# 4_PowerSupplie.net
KiCad netlist of a schematic drawn in Altium Designer
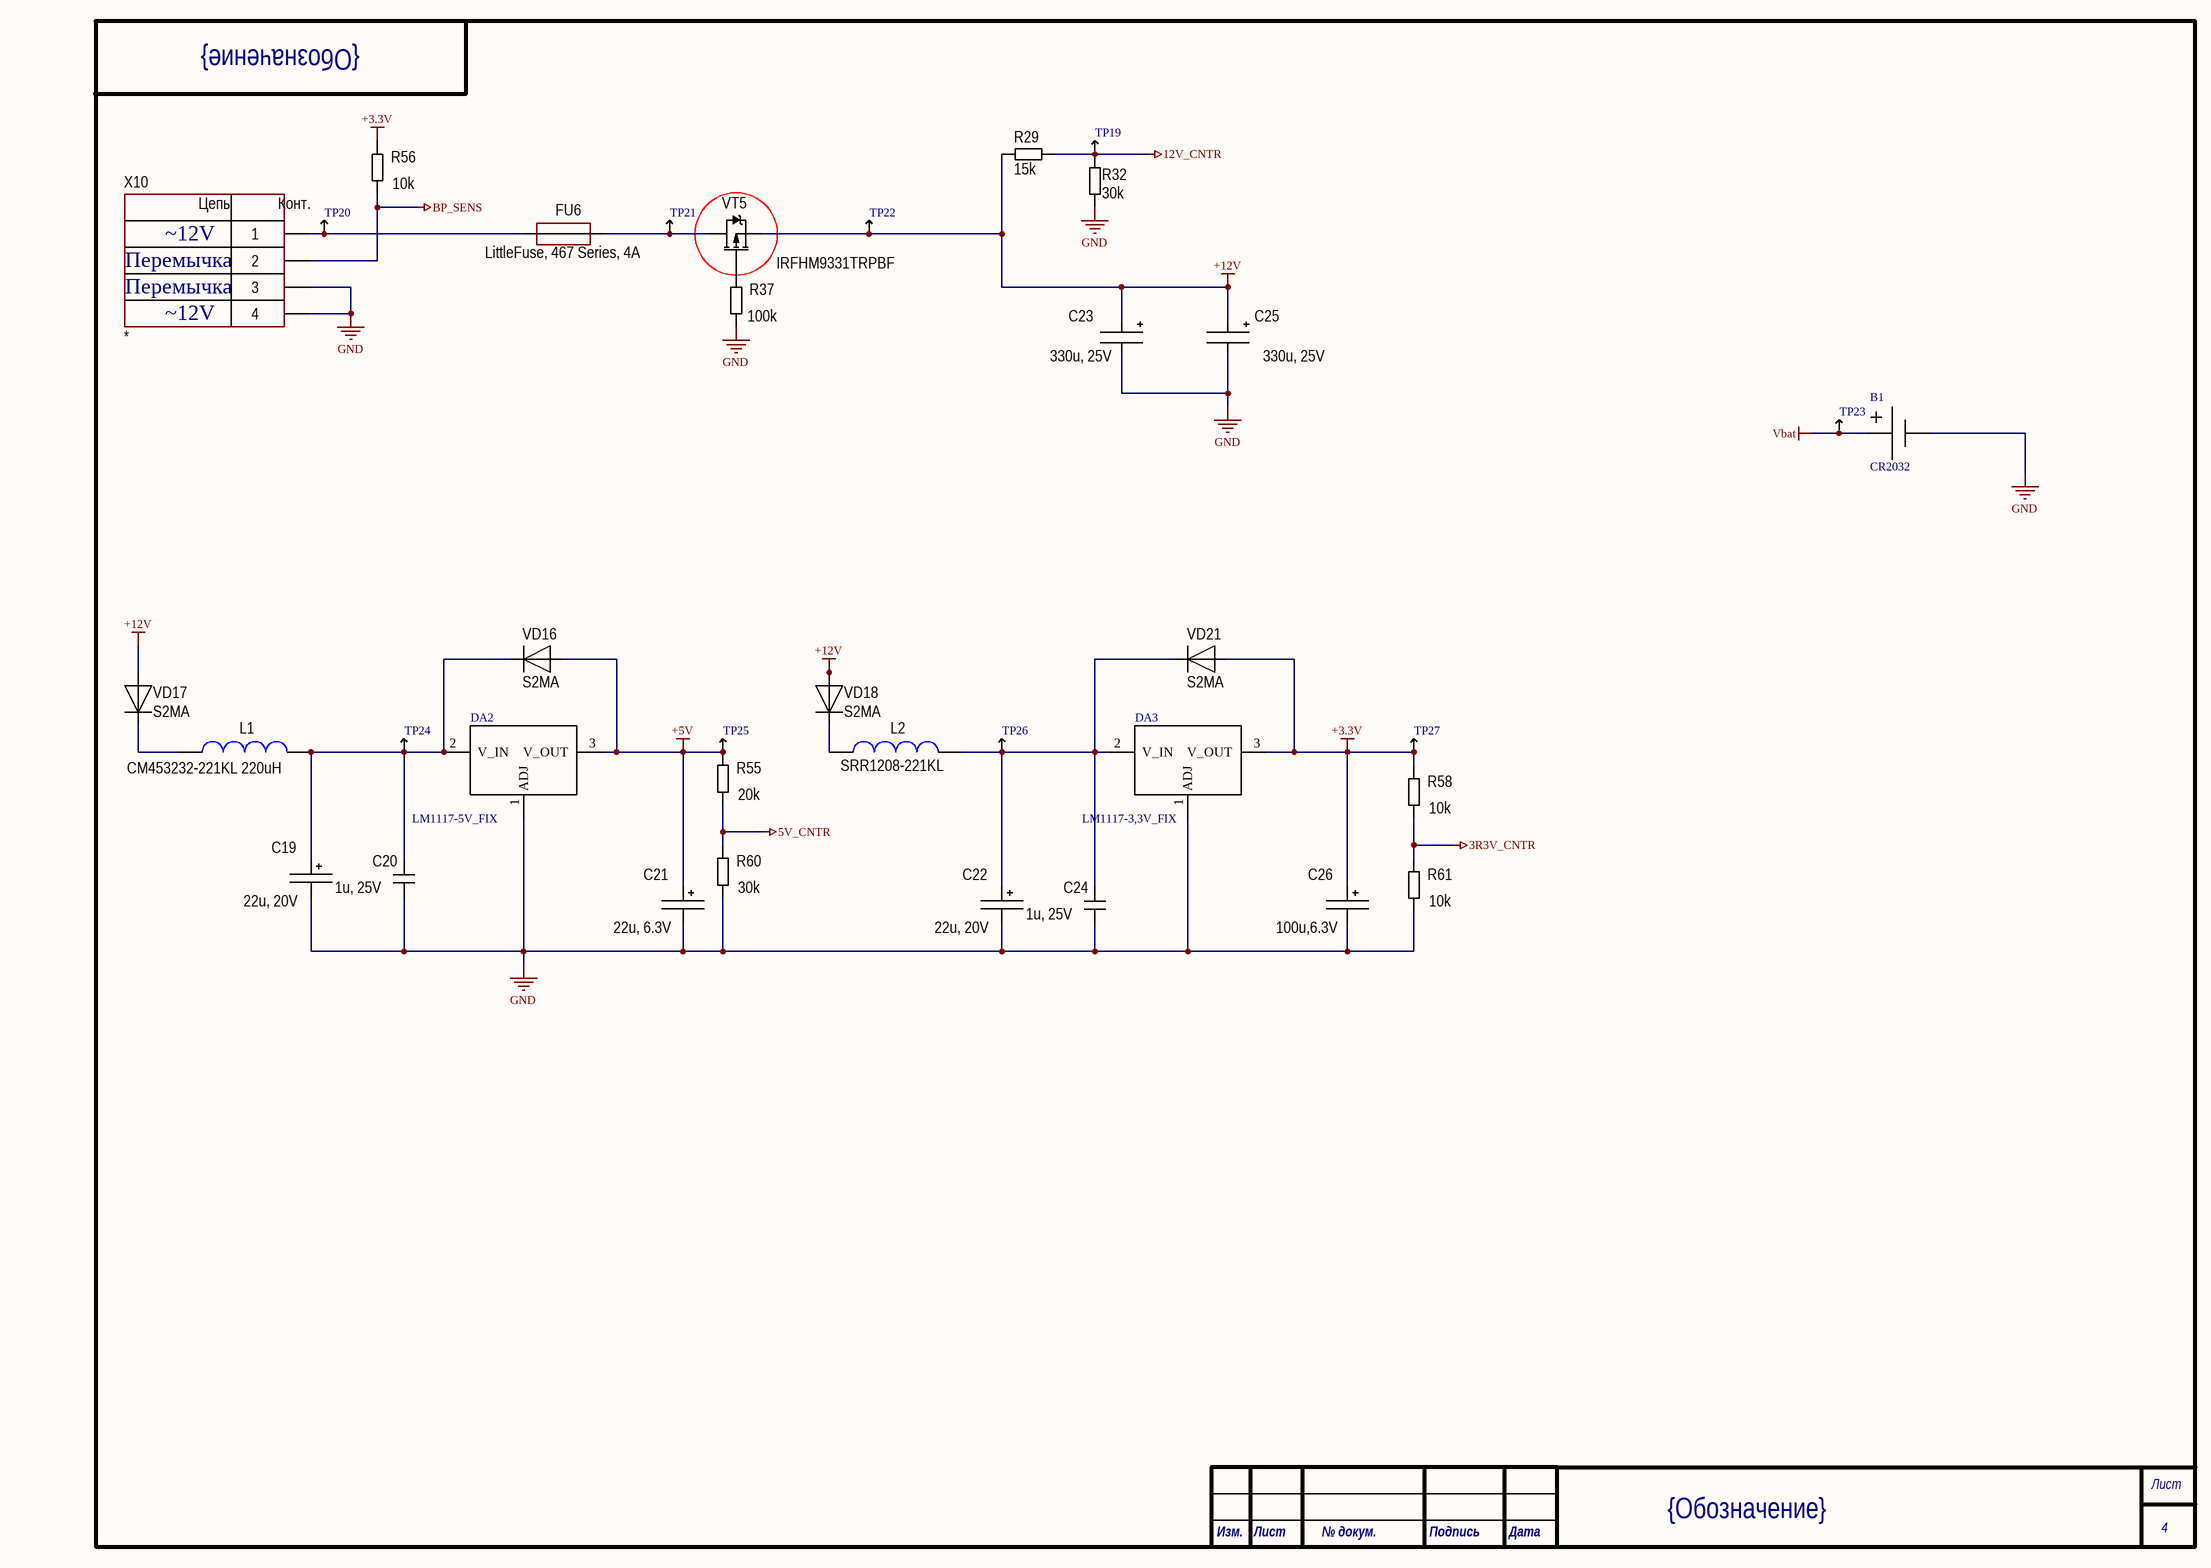
[diagram p0: 4_PowerSupplie.SchDoc]

(export (version "E")
  (design (tool "Eeschema 10.0.6"))
  (components
    (comp (ref "B1")
      (value "CR2032")
      (footprint "CR2032")
      (libsource (lib "Melochi") (part "Battery_CR2032"))
    )
    (comp (ref "C19")
      (value "22u, 20V")
      (footprint "TANTAL_B")
      (libsource (lib "Condensators") (part "TantalCap"))
    )
    (comp (ref "C20")
      (value "1u, 25V")
      (footprint "CH0805C")
      (libsource (lib "Condensators") (part "Capacitor"))
    )
    (comp (ref "C21")
      (value "22u, 6.3V")
      (footprint "TANTAL_B")
      (libsource (lib "Condensators") (part "TantalCap"))
    )
    (comp (ref "C22")
      (value "22u, 20V")
      (footprint "TANTAL_B")
      (libsource (lib "Condensators") (part "TantalCap"))
    )
    (comp (ref "C23")
      (value "330u, 25V")
      (footprint "D10C4.4H10")
      (libsource (lib "Condensators") (part "AlumCap"))
    )
    (comp (ref "C24")
      (value "1u, 25V")
      (footprint "CH0805C")
      (libsource (lib "Condensators") (part "Capacitor"))
    )
    (comp (ref "C25")
      (value "330u, 25V")
      (footprint "D10C4.4H10")
      (libsource (lib "Condensators") (part "AlumCap"))
    )
    (comp (ref "C26")
      (value "100u,6.3V")
      (footprint "TANTAL_B")
      (libsource (lib "Condensators") (part "TantalCap"))
    )
    (comp (ref "DA2")
      (value "LM1117-5V_FIX")
      (footprint "SOT223_123")
      (libsource (lib "MicroIC") (part "LM1117"))
    )
    (comp (ref "DA3")
      (value "LM1117-3,3V_FIX")
      (footprint "SOT223_123")
      (libsource (lib "MicroIC") (part "LM1117"))
    )
    (comp (ref "FU6")
      (value "LittleFuse, 467 Series, 4A")
      (footprint "CH0603F")
      (libsource (lib "Melochi") (part "Fuse"))
    )
    (comp (ref "L1")
      (value "CM453232-221KL 220uH")
      (footprint "IND:1812")
      (libsource (lib "Inductance") (part "Inductor"))
    )
    (comp (ref "L2")
      (value "SRR1208-221KL")
      (footprint "IND: SRR1208")
      (libsource (lib "Inductance") (part "Inductor"))
    )
    (comp (ref "R29") (value "15k") (footprint "CH0805R") (libsource (lib "Resistors") (part "Resistor")))
    (comp (ref "R32") (value "30k") (footprint "CH0805R") (libsource (lib "Resistors") (part "Resistor")))
    (comp (ref "R37") (value "100k") (footprint "CH0805R") (libsource (lib "Resistors") (part "Resistor")))
    (comp (ref "R55") (value "20k") (footprint "CH0805R") (libsource (lib "Resistors") (part "Resistor")))
    (comp (ref "R56") (value "10k") (footprint "CH0805R") (libsource (lib "Resistors") (part "Resistor")))
    (comp (ref "R58") (value "10k") (footprint "CH0805R") (libsource (lib "Resistors") (part "Resistor")))
    (comp (ref "R60") (value "30k") (footprint "CH0805R") (libsource (lib "Resistors") (part "Resistor")))
    (comp (ref "R61") (value "10k") (footprint "CH0805R") (libsource (lib "Resistors") (part "Resistor")))
    (comp (ref "TP19") (value "TestPoint") (libsource (lib "BufLib") (part "TestPoint")))
    (comp (ref "TP20") (value "TestPoint") (libsource (lib "BufLib") (part "TestPoint")))
    (comp (ref "TP21") (value "TestPoint") (libsource (lib "BufLib") (part "TestPoint")))
    (comp (ref "TP22") (value "TestPoint") (libsource (lib "BufLib") (part "TestPoint")))
    (comp (ref "TP23") (value "TestPoint") (libsource (lib "BufLib") (part "TestPoint")))
    (comp (ref "TP24") (value "TestPoint") (libsource (lib "BufLib") (part "TestPoint")))
    (comp (ref "TP25") (value "TestPoint") (libsource (lib "BufLib") (part "TestPoint")))
    (comp (ref "TP26") (value "TestPoint") (libsource (lib "BufLib") (part "TestPoint")))
    (comp (ref "TP27") (value "TestPoint") (libsource (lib "BufLib") (part "TestPoint")))
    (comp (ref "VD16") (value "S2MA") (footprint "SMA") (libsource (lib "Diods") (part "Diod")))
    (comp (ref "VD17") (value "S2MA") (footprint "SMA") (libsource (lib "Diods") (part "Diod")))
    (comp (ref "VD18") (value "S2MA") (footprint "SMA") (libsource (lib "Diods") (part "Diod")))
    (comp (ref "VD21") (value "S2MA") (footprint "SMA") (libsource (lib "Diods") (part "Diod")))
    (comp (ref "VT5")
      (value "IRFHM9331TRPBF")
      (footprint "SOT223")
      (description "Mosfet")
      (libsource (lib "Tranzistor") (part "P-chanel"))
    )
    (comp (ref "X10")
      (value "*")
      (footprint "CON: CWF-4")
      (libsource (lib "Connectors") (part "4-Connector"))
    )
  )
  (nets
    (net (code "1") (name "+3.3V") (class "Default")
      (node (ref "C26") (pin "1") (pinfunction "1_1") (pintype "power_in"))
      (node (ref "DA3") (pin "3") (pinfunction "V_OUT_3") (pintype "passive"))
      (node (ref "R56") (pin "2") (pinfunction "2_2") (pintype "passive"))
      (node (ref "R58") (pin "2") (pinfunction "2_2") (pintype "passive"))
      (node (ref "TP27") (pin "0") (pinfunction "0_0") (pintype "passive"))
      (node (ref "VD21") (pin "1") (pinfunction "1_1") (pintype "passive"))
    )
    (net (code "2") (name "+5V") (class "Default")
      (node (ref "C21") (pin "1") (pinfunction "1_1") (pintype "power_in"))
      (node (ref "DA2") (pin "3") (pinfunction "V_OUT_3") (pintype "passive"))
      (node (ref "R55") (pin "2") (pinfunction "2_2") (pintype "passive"))
      (node (ref "TP25") (pin "0") (pinfunction "0_0") (pintype "passive"))
      (node (ref "VD16") (pin "1") (pinfunction "1_1") (pintype "passive"))
    )
    (net (code "3") (name "+12V") (class "Default")
      (node (ref "C23") (pin "1") (pinfunction "1_1") (pintype "power_in"))
      (node (ref "C25") (pin "1") (pinfunction "1_1") (pintype "power_in"))
      (node (ref "R29") (pin "2") (pinfunction "2_2") (pintype "passive"))
      (node (ref "TP22") (pin "0") (pinfunction "0_0") (pintype "passive"))
      (node (ref "VD17") (pin "1") (pinfunction "1_1") (pintype "passive"))
      (node (ref "VD18") (pin "1") (pinfunction "1_1") (pintype "passive"))
      (node (ref "VT5") (pin "3") (pinfunction "S_3") (pintype "passive"))
    )
    (net (code "4") (name "3R3V_CNTR") (class "Default")
      (node (ref "R58") (pin "1") (pinfunction "1_1") (pintype "passive"))
      (node (ref "R61") (pin "2") (pinfunction "2_2") (pintype "passive"))
    )
    (net (code "5") (name "5V_CNTR") (class "Default")
      (node (ref "R55") (pin "1") (pinfunction "1_1") (pintype "passive"))
      (node (ref "R60") (pin "2") (pinfunction "2_2") (pintype "passive"))
    )
    (net (code "6") (name "12V_CNTR") (class "Default")
      (node (ref "R29") (pin "1") (pinfunction "1_1") (pintype "passive"))
      (node (ref "R32") (pin "2") (pinfunction "2_2") (pintype "passive"))
      (node (ref "TP19") (pin "0") (pinfunction "0_0") (pintype "passive"))
    )
    (net (code "7") (name "BP_SENS") (class "Default")
      (node (ref "R56") (pin "1") (pinfunction "1_1") (pintype "passive"))
      (node (ref "X10") (pin "2") (pinfunction "2_2") (pintype "passive"))
    )
    (net (code "8") (name "GND") (class "Default")
      (node (ref "B1") (pin "2") (pinfunction "2_2") (pintype "passive"))
      (node (ref "C19") (pin "2") (pinfunction "2_2") (pintype "power_in"))
      (node (ref "C20") (pin "1") (pinfunction "1_1") (pintype "passive"))
      (node (ref "C21") (pin "2") (pinfunction "2_2") (pintype "power_in"))
      (node (ref "C22") (pin "2") (pinfunction "2_2") (pintype "power_in"))
      (node (ref "C23") (pin "2") (pinfunction "2_2") (pintype "power_in"))
      (node (ref "C24") (pin "1") (pinfunction "1_1") (pintype "passive"))
      (node (ref "C25") (pin "2") (pinfunction "2_2") (pintype "power_in"))
      (node (ref "C26") (pin "2") (pinfunction "2_2") (pintype "power_in"))
      (node (ref "DA2") (pin "1") (pinfunction "ADJ_1") (pintype "passive"))
      (node (ref "DA3") (pin "1") (pinfunction "ADJ_1") (pintype "passive"))
      (node (ref "R32") (pin "1") (pinfunction "1_1") (pintype "passive"))
      (node (ref "R37") (pin "1") (pinfunction "1_1") (pintype "passive"))
      (node (ref "R60") (pin "1") (pinfunction "1_1") (pintype "passive"))
      (node (ref "R61") (pin "1") (pinfunction "1_1") (pintype "passive"))
      (node (ref "X10") (pin "3") (pinfunction "3_3") (pintype "power_in"))
      (node (ref "X10") (pin "4") (pinfunction "4_4") (pintype "power_in"))
    )
    (net (code "9") (name "Net-(DA2-V_IN)") (class "Default")
      (node (ref "C19") (pin "1") (pinfunction "1_1") (pintype "power_in"))
      (node (ref "C20") (pin "2") (pinfunction "2_2") (pintype "passive"))
      (node (ref "DA2") (pin "2") (pinfunction "V_IN_2") (pintype "passive"))
      (node (ref "L1") (pin "1") (pinfunction "1_1") (pintype "passive"))
      (node (ref "TP24") (pin "0") (pinfunction "0_0") (pintype "passive"))
      (node (ref "VD16") (pin "2") (pinfunction "2_2") (pintype "passive"))
    )
    (net (code "10") (name "Net-(DA3-V_IN)") (class "Default")
      (node (ref "C22") (pin "1") (pinfunction "1_1") (pintype "power_in"))
      (node (ref "C24") (pin "2") (pinfunction "2_2") (pintype "passive"))
      (node (ref "DA3") (pin "2") (pinfunction "V_IN_2") (pintype "passive"))
      (node (ref "L2") (pin "1") (pinfunction "1_1") (pintype "passive"))
      (node (ref "TP26") (pin "0") (pinfunction "0_0") (pintype "passive"))
      (node (ref "VD21") (pin "2") (pinfunction "2_2") (pintype "passive"))
    )
    (net (code "11") (name "Net-(FU6-Pad1)") (class "Default")
      (node (ref "FU6") (pin "1") (pinfunction "1_1") (pintype "passive"))
      (node (ref "TP20") (pin "0") (pinfunction "0_0") (pintype "passive"))
      (node (ref "X10") (pin "1") (pinfunction "1_1") (pintype "passive"))
    )
    (net (code "12") (name "Net-(L1-Pad2)") (class "Default")
      (node (ref "L1") (pin "2") (pinfunction "2_2") (pintype "passive"))
      (node (ref "VD17") (pin "2") (pinfunction "2_2") (pintype "passive"))
    )
    (net (code "13") (name "Net-(L2-Pad2)") (class "Default")
      (node (ref "L2") (pin "2") (pinfunction "2_2") (pintype "passive"))
      (node (ref "VD18") (pin "2") (pinfunction "2_2") (pintype "passive"))
    )
    (net (code "14") (name "Net-(VT5-D)") (class "Default")
      (node (ref "FU6") (pin "2") (pinfunction "2_2") (pintype "passive"))
      (node (ref "TP21") (pin "0") (pinfunction "0_0") (pintype "passive"))
      (node (ref "VT5") (pin "2") (pinfunction "D_2") (pintype "passive"))
    )
    (net (code "15") (name "Net-(VT5-G)") (class "Default")
      (node (ref "R37") (pin "2") (pinfunction "2_2") (pintype "passive"))
      (node (ref "VT5") (pin "1") (pinfunction "G_1") (pintype "passive"))
    )
    (net (code "16") (name "Vbat") (class "Default")
      (node (ref "B1") (pin "1") (pinfunction "1_1") (pintype "passive"))
      (node (ref "TP23") (pin "0") (pinfunction "0_0") (pintype "passive"))
    )
  )
)
